# MEMORY.net
KiCad netlist of a schematic drawn in Altium Designer
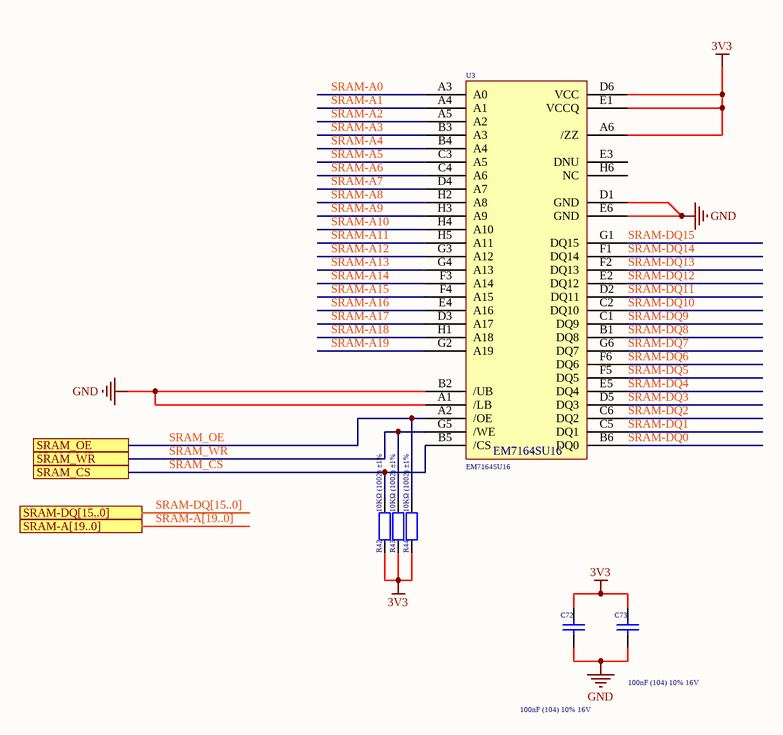
[diagram p0: MEMORY.SchDoc]

(export (version "E")
  (design (tool "Eeschema 10.0.6"))
  (components
    (comp (ref "C72")
      (value "100nF (104) 10% 16V")
      (footprint "0402_C")
      (description "贴片电容")
      (libsource (lib "Miscellaneous Devices LC") (part "0402 100nF (104) 10% 16V"))
    )
    (comp (ref "C73")
      (value "100nF (104) 10% 16V")
      (footprint "0402_C")
      (description "贴片电容")
      (libsource (lib "Miscellaneous Devices LC") (part "0402 100nF (104) 10% 16V"))
    )
    (comp (ref "R42")
      (value "10KΩ (1002) ±1%")
      (footprint "0402_R")
      (description "贴片电阻")
      (libsource (lib "Miscellaneous Devices LC") (part "0402 10KΩ (1002) 1%"))
    )
    (comp (ref "R43")
      (value "10KΩ (1002) ±1%")
      (footprint "0402_R")
      (description "贴片电阻")
      (libsource (lib "Miscellaneous Devices LC") (part "0402 10KΩ (1002) 1%"))
    )
    (comp (ref "R44")
      (value "10KΩ (1002) ±1%")
      (footprint "0402_R")
      (description "贴片电阻")
      (libsource (lib "Miscellaneous Devices LC") (part "0402 10KΩ (1002) 1%"))
    )
    (comp (ref "U3")
      (value "EM7164SU16")
      (footprint "BGA48C75P6X8_598X698X104")
      (libsource (lib "2号库") (part "EM7164SU16"))
    )
  )
  (nets
    (net (code "1") (name "/SRAM-A0") (class "Default")
      (node (ref "U3") (pin "A3") (pinfunction "A0_A3") (pintype "passive"))
    )
    (net (code "2") (name "/SRAM-A1") (class "Default")
      (node (ref "U3") (pin "A4") (pinfunction "A1_A4") (pintype "passive"))
    )
    (net (code "3") (name "/SRAM-A2") (class "Default")
      (node (ref "U3") (pin "A5") (pinfunction "A2_A5") (pintype "passive"))
    )
    (net (code "4") (name "/SRAM-A3") (class "Default")
      (node (ref "U3") (pin "B3") (pinfunction "A3_B3") (pintype "passive"))
    )
    (net (code "5") (name "/SRAM-A4") (class "Default")
      (node (ref "U3") (pin "B4") (pinfunction "A4_B4") (pintype "passive"))
    )
    (net (code "6") (name "/SRAM-A5") (class "Default")
      (node (ref "U3") (pin "C3") (pinfunction "A5_C3") (pintype "passive"))
    )
    (net (code "7") (name "/SRAM-A6") (class "Default")
      (node (ref "U3") (pin "C4") (pinfunction "A6_C4") (pintype "passive"))
    )
    (net (code "8") (name "/SRAM-A7") (class "Default")
      (node (ref "U3") (pin "D4") (pinfunction "A7_D4") (pintype "passive"))
    )
    (net (code "9") (name "/SRAM-A8") (class "Default")
      (node (ref "U3") (pin "H2") (pinfunction "A8_H2") (pintype "passive"))
    )
    (net (code "10") (name "/SRAM-A9") (class "Default")
      (node (ref "U3") (pin "H3") (pinfunction "A9_H3") (pintype "passive"))
    )
    (net (code "11") (name "/SRAM-A10") (class "Default")
      (node (ref "U3") (pin "H4") (pinfunction "A10_H4") (pintype "passive"))
    )
    (net (code "12") (name "/SRAM-A11") (class "Default")
      (node (ref "U3") (pin "H5") (pinfunction "A11_H5") (pintype "passive"))
    )
    (net (code "13") (name "/SRAM-A12") (class "Default")
      (node (ref "U3") (pin "G3") (pinfunction "A12_G3") (pintype "passive"))
    )
    (net (code "14") (name "/SRAM-A13") (class "Default")
      (node (ref "U3") (pin "G4") (pinfunction "A13_G4") (pintype "passive"))
    )
    (net (code "15") (name "/SRAM-A14") (class "Default")
      (node (ref "U3") (pin "F3") (pinfunction "A14_F3") (pintype "passive"))
    )
    (net (code "16") (name "/SRAM-A15") (class "Default")
      (node (ref "U3") (pin "F4") (pinfunction "A15_F4") (pintype "passive"))
    )
    (net (code "17") (name "/SRAM-A16") (class "Default")
      (node (ref "U3") (pin "E4") (pinfunction "A16_E4") (pintype "passive"))
    )
    (net (code "18") (name "/SRAM-A17") (class "Default")
      (node (ref "U3") (pin "D3") (pinfunction "A17_D3") (pintype "passive"))
    )
    (net (code "19") (name "/SRAM-A18") (class "Default")
      (node (ref "U3") (pin "H1") (pinfunction "A18_H1") (pintype "passive"))
    )
    (net (code "20") (name "/SRAM-A19") (class "Default")
      (node (ref "U3") (pin "G2") (pinfunction "A19_G2") (pintype "passive"))
    )
    (net (code "22") (name "/SRAM-DQ0") (class "Default")
      (node (ref "U3") (pin "B6") (pinfunction "DQ0_B6") (pintype "passive"))
    )
    (net (code "23") (name "/SRAM-DQ1") (class "Default")
      (node (ref "U3") (pin "C5") (pinfunction "DQ1_C5") (pintype "passive"))
    )
    (net (code "24") (name "/SRAM-DQ2") (class "Default")
      (node (ref "U3") (pin "C6") (pinfunction "DQ2_C6") (pintype "passive"))
    )
    (net (code "25") (name "/SRAM-DQ3") (class "Default")
      (node (ref "U3") (pin "D5") (pinfunction "DQ3_D5") (pintype "passive"))
    )
    (net (code "26") (name "/SRAM-DQ4") (class "Default")
      (node (ref "U3") (pin "E5") (pinfunction "DQ4_E5") (pintype "passive"))
    )
    (net (code "27") (name "/SRAM-DQ5") (class "Default")
      (node (ref "U3") (pin "F5") (pinfunction "DQ5_F5") (pintype "passive"))
    )
    (net (code "28") (name "/SRAM-DQ6") (class "Default")
      (node (ref "U3") (pin "F6") (pinfunction "DQ6_F6") (pintype "passive"))
    )
    (net (code "29") (name "/SRAM-DQ7") (class "Default")
      (node (ref "U3") (pin "G6") (pinfunction "DQ7_G6") (pintype "passive"))
    )
    (net (code "30") (name "/SRAM-DQ8") (class "Default")
      (node (ref "U3") (pin "B1") (pinfunction "DQ8_B1") (pintype "passive"))
    )
    (net (code "31") (name "/SRAM-DQ9") (class "Default")
      (node (ref "U3") (pin "C1") (pinfunction "DQ9_C1") (pintype "passive"))
    )
    (net (code "32") (name "/SRAM-DQ10") (class "Default")
      (node (ref "U3") (pin "C2") (pinfunction "DQ10_C2") (pintype "passive"))
    )
    (net (code "33") (name "/SRAM-DQ11") (class "Default")
      (node (ref "U3") (pin "D2") (pinfunction "DQ11_D2") (pintype "passive"))
    )
    (net (code "34") (name "/SRAM-DQ12") (class "Default")
      (node (ref "U3") (pin "E2") (pinfunction "DQ12_E2") (pintype "passive"))
    )
    (net (code "35") (name "/SRAM-DQ13") (class "Default")
      (node (ref "U3") (pin "F2") (pinfunction "DQ13_F2") (pintype "passive"))
    )
    (net (code "36") (name "/SRAM-DQ14") (class "Default")
      (node (ref "U3") (pin "F1") (pinfunction "DQ14_F1") (pintype "passive"))
    )
    (net (code "37") (name "/SRAM-DQ15") (class "Default")
      (node (ref "U3") (pin "G1") (pinfunction "DQ15_G1") (pintype "passive"))
    )
    (net (code "39") (name "/SRAM_CS") (class "Default")
      (node (ref "R42") (pin "2") (pinfunction "2_2") (pintype "passive"))
      (node (ref "U3") (pin "B5") (pinfunction "/CS_B5") (pintype "passive"))
    )
    (net (code "40") (name "/SRAM_OE") (class "Default")
      (node (ref "R44") (pin "2") (pinfunction "2_2") (pintype "passive"))
      (node (ref "U3") (pin "A2") (pinfunction "/OE_A2") (pintype "passive"))
    )
    (net (code "41") (name "/SRAM_WR") (class "Default")
      (node (ref "R43") (pin "2") (pinfunction "2_2") (pintype "passive"))
      (node (ref "U3") (pin "G5") (pinfunction "/WE_G5") (pintype "passive"))
    )
    (net (code "42") (name "3V3") (class "Default")
      (node (ref "C72") (pin "2") (pinfunction "2_2") (pintype "passive"))
      (node (ref "C73") (pin "2") (pinfunction "2_2") (pintype "passive"))
      (node (ref "R42") (pin "1") (pinfunction "1_1") (pintype "passive"))
      (node (ref "R43") (pin "1") (pinfunction "1_1") (pintype "passive"))
      (node (ref "R44") (pin "1") (pinfunction "1_1") (pintype "passive"))
      (node (ref "U3") (pin "A6") (pinfunction "/ZZ_A6") (pintype "passive"))
      (node (ref "U3") (pin "D6") (pinfunction "VCC_D6") (pintype "passive"))
      (node (ref "U3") (pin "E1") (pinfunction "VCCQ_E1") (pintype "passive"))
    )
    (net (code "43") (name "GND") (class "Default")
      (node (ref "C72") (pin "1") (pinfunction "1_1") (pintype "passive"))
      (node (ref "C73") (pin "1") (pinfunction "1_1") (pintype "passive"))
      (node (ref "U3") (pin "A1") (pinfunction "/LB_A1") (pintype "passive"))
      (node (ref "U3") (pin "B2") (pinfunction "/UB_B2") (pintype "passive"))
      (node (ref "U3") (pin "D1") (pinfunction "GND_D1") (pintype "passive"))
      (node (ref "U3") (pin "E6") (pinfunction "GND_E6") (pintype "passive"))
    )
    (net (code "44") (name "unconnected-(U3-DNU-PadE3)") (class "Default")
      (node (ref "U3") (pin "E3") (pinfunction "DNU_E3") (pintype "passive"))
    )
    (net (code "45") (name "unconnected-(U3-NC-PadH6)") (class "Default")
      (node (ref "U3") (pin "H6") (pinfunction "NC_H6") (pintype "passive"))
    )
  )
)
